# T2M_4_0.net
KiCad netlist of a schematic drawn in EAGLE
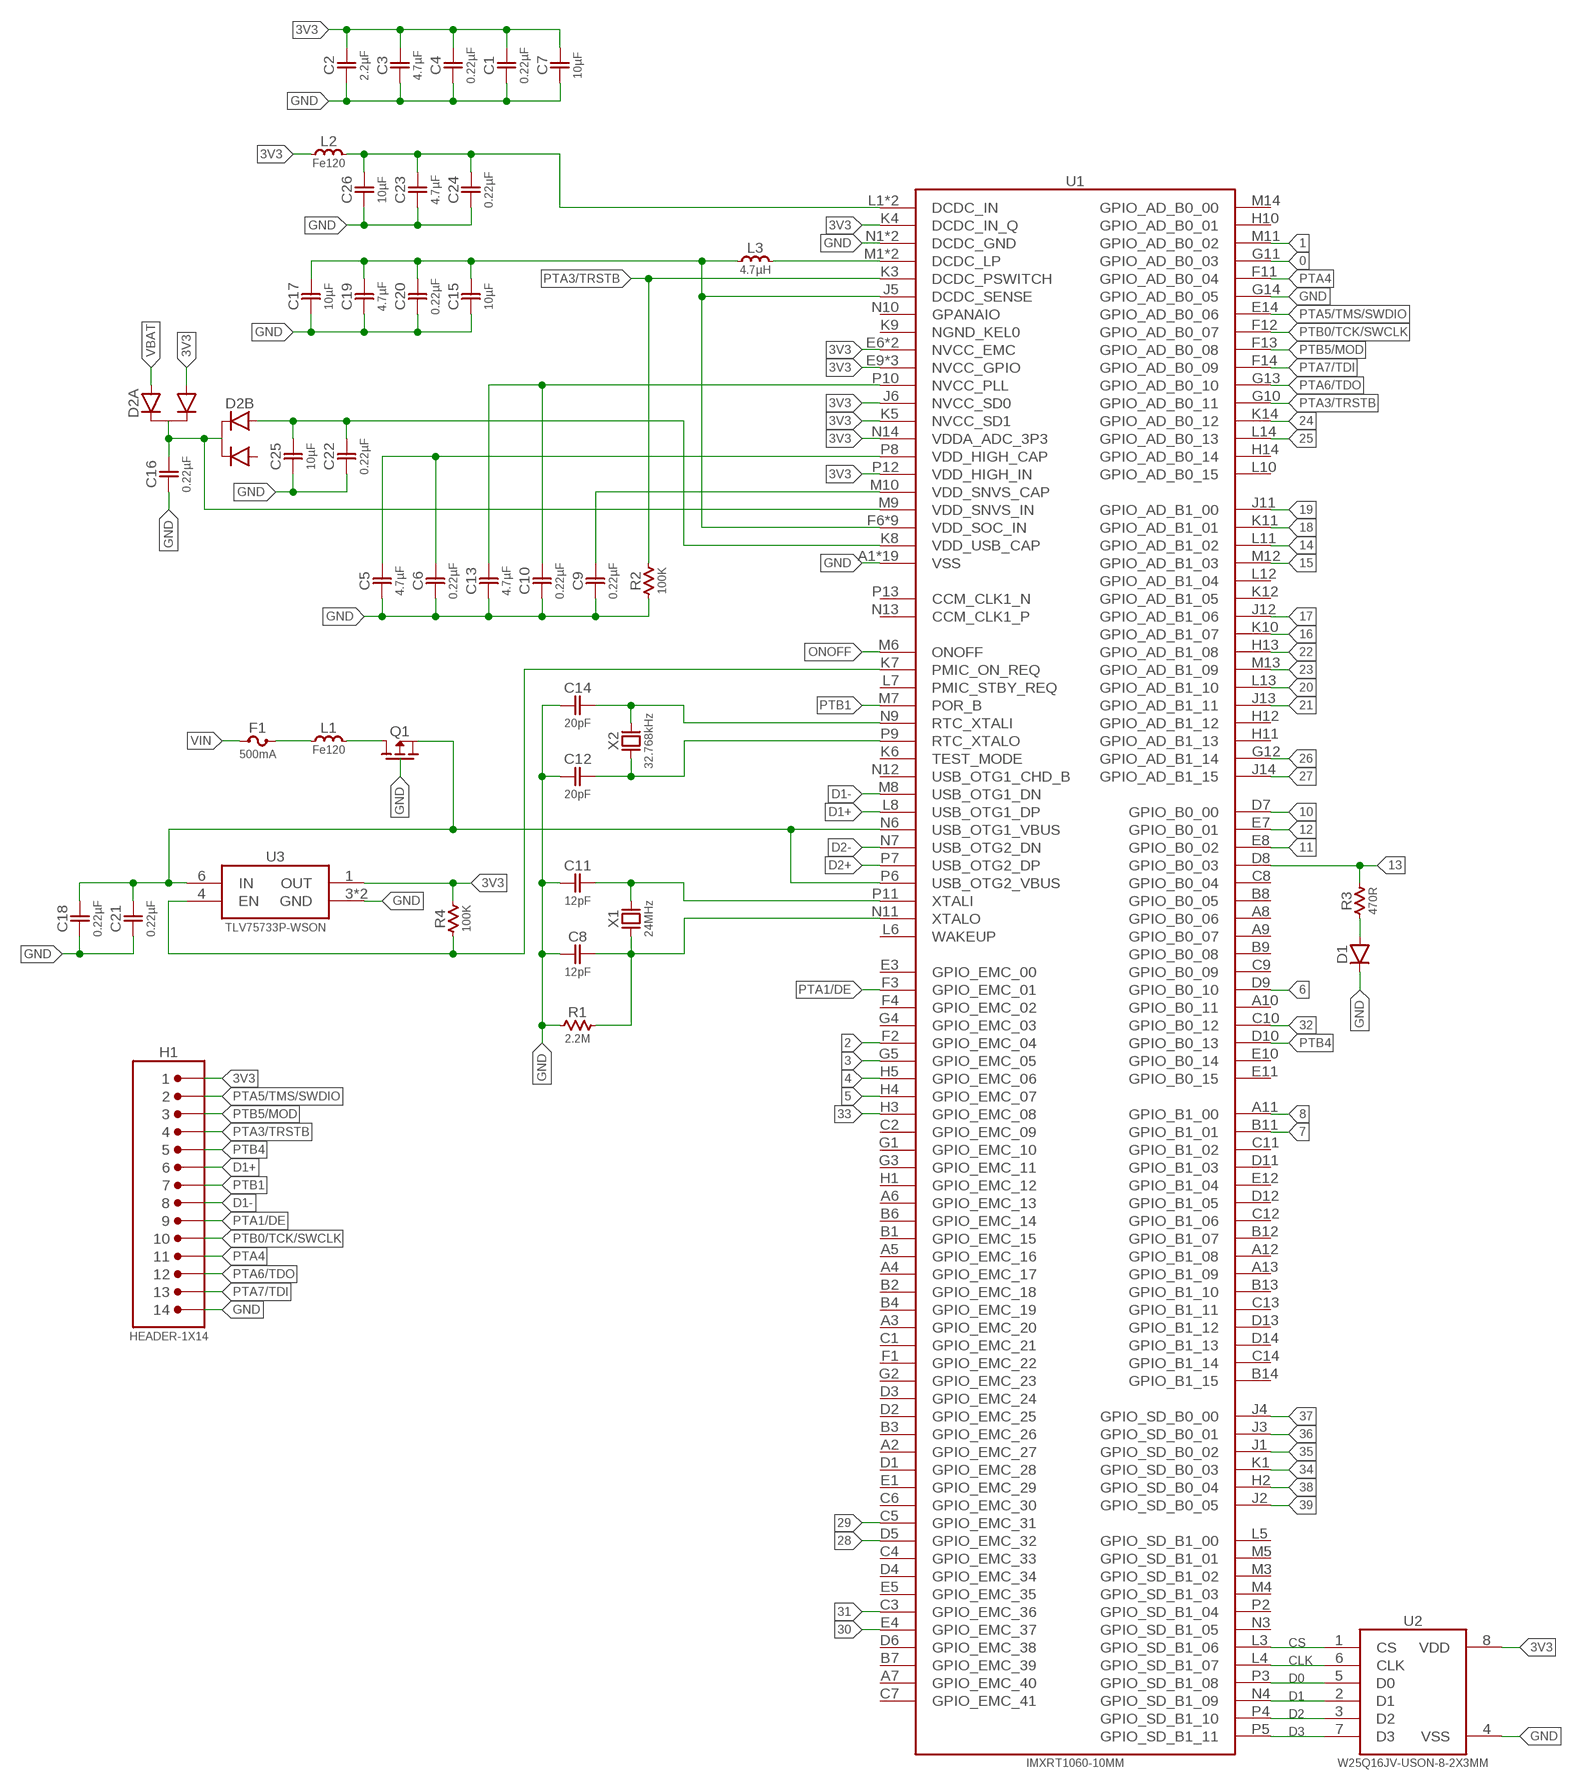
[diagram p0: schematic, sheet 1]
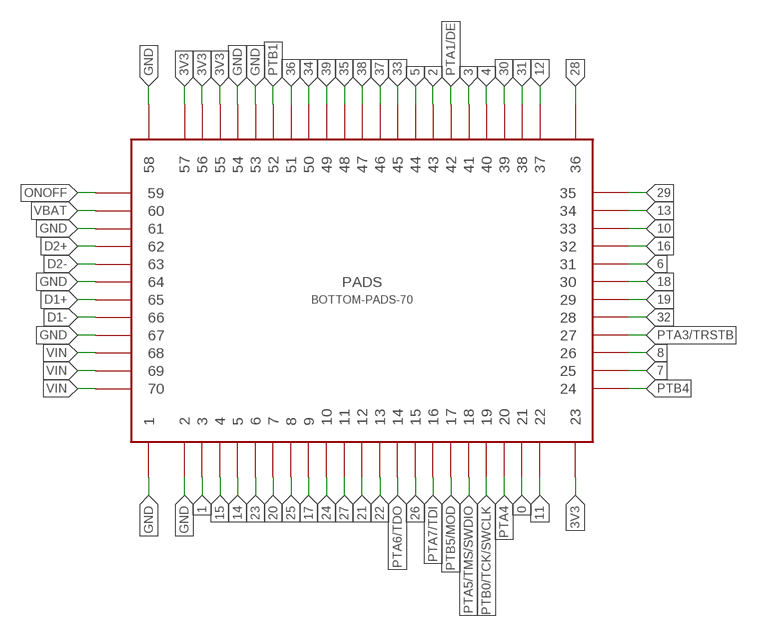
[diagram p1: schematic, sheet 2]

(export (version "E")
  (design (tool "Eeschema 10.0.6"))
  (components
    (comp (ref "C1")
      (value "0.22µF")
      (footprint "eagle-import:0402-NP")
      (libsource (lib "eagle-import") (part "CAP-NP-0402"))
    )
    (comp (ref "C2")
      (value "2.2µF")
      (footprint "eagle-import:0402-NP")
      (libsource (lib "eagle-import") (part "CAP-NP-0402"))
    )
    (comp (ref "C3")
      (value "4.7µF")
      (footprint "eagle-import:0402-NP")
      (libsource (lib "eagle-import") (part "CAP-NP-0402"))
    )
    (comp (ref "C4")
      (value "0.22µF")
      (footprint "eagle-import:0402-NP")
      (libsource (lib "eagle-import") (part "CAP-NP-0402"))
    )
    (comp (ref "C5")
      (value "4.7µF")
      (footprint "eagle-import:0402-NP")
      (libsource (lib "eagle-import") (part "CAP-NP-0402"))
    )
    (comp (ref "C6")
      (value "0.22µF")
      (footprint "eagle-import:0402-NP")
      (libsource (lib "eagle-import") (part "CAP-NP-0402"))
    )
    (comp (ref "C7")
      (value "10µF")
      (footprint "eagle-import:0603-NP")
      (libsource (lib "eagle-import") (part "CAP-NP-0603"))
    )
    (comp (ref "C8")
      (value "12pF")
      (footprint "eagle-import:0402-NP")
      (libsource (lib "eagle-import") (part "CAP-NP-0402"))
    )
    (comp (ref "C9")
      (value "0.22µF")
      (footprint "eagle-import:0402-NP")
      (libsource (lib "eagle-import") (part "CAP-NP-0402"))
    )
    (comp (ref "C10")
      (value "0.22µF")
      (footprint "eagle-import:0402-NP")
      (libsource (lib "eagle-import") (part "CAP-NP-0402"))
    )
    (comp (ref "C11")
      (value "12pF")
      (footprint "eagle-import:0402-NP")
      (libsource (lib "eagle-import") (part "CAP-NP-0402"))
    )
    (comp (ref "C12")
      (value "20pF")
      (footprint "eagle-import:0402-NP")
      (libsource (lib "eagle-import") (part "CAP-NP-0402"))
    )
    (comp (ref "C13")
      (value "4.7µF")
      (footprint "eagle-import:0402-NP")
      (libsource (lib "eagle-import") (part "CAP-NP-0402"))
    )
    (comp (ref "C14")
      (value "20pF")
      (footprint "eagle-import:0402-NP")
      (libsource (lib "eagle-import") (part "CAP-NP-0402"))
    )
    (comp (ref "C15")
      (value "10µF")
      (footprint "eagle-import:0603-NP")
      (libsource (lib "eagle-import") (part "CAP-NP-0603"))
    )
    (comp (ref "C16")
      (value "0.22µF")
      (footprint "eagle-import:0402-NP")
      (libsource (lib "eagle-import") (part "CAP-NP-0402"))
    )
    (comp (ref "C17")
      (value "10µF")
      (footprint "eagle-import:0603-NP")
      (libsource (lib "eagle-import") (part "CAP-NP-0603"))
    )
    (comp (ref "C18")
      (value "0.22µF")
      (footprint "eagle-import:0402-NP")
      (libsource (lib "eagle-import") (part "CAP-NP-0402"))
    )
    (comp (ref "C19")
      (value "4.7µF")
      (footprint "eagle-import:0402-NP")
      (libsource (lib "eagle-import") (part "CAP-NP-0402"))
    )
    (comp (ref "C20")
      (value "0.22µF")
      (footprint "eagle-import:0402-NP")
      (libsource (lib "eagle-import") (part "CAP-NP-0402"))
    )
    (comp (ref "C21")
      (value "0.22µF")
      (footprint "eagle-import:0402-NP")
      (libsource (lib "eagle-import") (part "CAP-NP-0402"))
    )
    (comp (ref "C22")
      (value "0.22µF")
      (footprint "eagle-import:0402-NP")
      (libsource (lib "eagle-import") (part "CAP-NP-0402"))
    )
    (comp (ref "C23")
      (value "4.7µF")
      (footprint "eagle-import:0402-NP")
      (libsource (lib "eagle-import") (part "CAP-NP-0402"))
    )
    (comp (ref "C24")
      (value "0.22µF")
      (footprint "eagle-import:0402-NP")
      (libsource (lib "eagle-import") (part "CAP-NP-0402"))
    )
    (comp (ref "C25")
      (value "10µF")
      (footprint "eagle-import:0603-NP")
      (libsource (lib "eagle-import") (part "CAP-NP-0603"))
    )
    (comp (ref "C26")
      (value "10µF")
      (footprint "eagle-import:0603-NP")
      (libsource (lib "eagle-import") (part "CAP-NP-0603"))
    )
    (comp (ref "D1")
      (value "DIODE-0402")
      (footprint "eagle-import:0402-P")
      (libsource (lib "eagle-import") (part "DIODE-0402"))
    )
    (comp (ref "D2")
      (value "BAT54C-2-SOT-666")
      (footprint "eagle-import:SOT-666")
      (libsource (lib "eagle-import") (part "BAT54C-2-SOT-666"))
    )
    (comp (ref "F1")
      (value "500mA")
      (footprint "eagle-import:0603-NP")
      (libsource (lib "eagle-import") (part "FUSE-0603"))
    )
    (comp (ref "H1")
      (value "HEADER-1X14")
      (footprint "eagle-import:2X7-1.27MM")
      (libsource (lib "eagle-import") (part "HEADER-1X14"))
    )
    (comp (ref "L1")
      (value "Fe120")
      (footprint "eagle-import:0402-NP")
      (libsource (lib "eagle-import") (part "INDUCTOR-0402"))
    )
    (comp (ref "L2")
      (value "Fe120")
      (footprint "eagle-import:0402-NP")
      (libsource (lib "eagle-import") (part "INDUCTOR-0402"))
    )
    (comp (ref "L3")
      (value "4.7µH")
      (footprint "eagle-import:0603-NP")
      (libsource (lib "eagle-import") (part "INDUCTOR-0603"))
    )
    (comp (ref "Q1")
      (value "MOSFET-P")
      (footprint "eagle-import:SOT-23")
      (libsource (lib "eagle-import") (part "MOSFET-P"))
    )
    (comp (ref "R1")
      (value "2.2M")
      (footprint "eagle-import:0402-NP")
      (libsource (lib "eagle-import") (part "RESISTOR-0402"))
    )
    (comp (ref "R2")
      (value "100K")
      (footprint "eagle-import:0402-NP")
      (libsource (lib "eagle-import") (part "RESISTOR-0402"))
    )
    (comp (ref "R3")
      (value "470R")
      (footprint "eagle-import:0402-NP")
      (libsource (lib "eagle-import") (part "RESISTOR-0402"))
    )
    (comp (ref "R4")
      (value "100K")
      (footprint "eagle-import:0402-NP")
      (libsource (lib "eagle-import") (part "RESISTOR-0402"))
    )
    (comp (ref "U1")
      (value "IMXRT1060-10MM")
      (footprint "eagle-import:BGA-196-10MM")
      (libsource (lib "eagle-import") (part "IMXRT1060-10MM"))
    )
    (comp (ref "U2")
      (value "W25Q16JV-USON-8-2X3MM")
      (footprint "eagle-import:USON-8-2X3MM")
      (libsource (lib "eagle-import") (part "W25Q16JV-USON-8-2X3MM"))
    )
    (comp (ref "U3")
      (value "TLV75733P-WSON")
      (footprint "eagle-import:WSON-6")
      (libsource (lib "eagle-import") (part "TLV75733P-WSON"))
    )
    (comp (ref "X1")
      (value "24MHz")
      (footprint "eagle-import:CRYSTAL-2X1.6MM")
      (libsource (lib "eagle-import") (part "CRYSTAL-2X1.6MM"))
    )
    (comp (ref "X2")
      (value "32.768kHz")
      (footprint "eagle-import:CRYSTAL-2X1.2MM")
      (libsource (lib "eagle-import") (part "CRYSTAL-2X1.2MM"))
    )
    (comp (ref "PADS")
      (value "BOTTOM-PADS-70")
      (footprint "eagle-import:BOTTOM-PADS-70")
      (libsource (lib "eagle-import") (part "BOTTOM-PADS-70"))
    )
  )
  (nets
    (net (code "1") (name "0") (class "Default")
      (node (ref "PADS") (pin "21") (pinfunction "21_21") (pintype "bidirectional"))
      (node (ref "U1") (pin "G11") (pinfunction "GPIO_AD_B0_03_G11") (pintype "bidirectional"))
    )
    (net (code "2") (name "1") (class "Default")
      (node (ref "PADS") (pin "3") (pinfunction "3_3") (pintype "bidirectional"))
      (node (ref "U1") (pin "M11") (pinfunction "GPIO_AD_B0_02_M11") (pintype "bidirectional"))
    )
    (net (code "3") (name "2") (class "Default")
      (node (ref "PADS") (pin "43") (pinfunction "43_43") (pintype "bidirectional"))
      (node (ref "U1") (pin "F2") (pinfunction "GPIO_EMC_04_F2") (pintype "bidirectional"))
    )
    (net (code "4") (name "3") (class "Default")
      (node (ref "PADS") (pin "41") (pinfunction "41_41") (pintype "bidirectional"))
      (node (ref "U1") (pin "G5") (pinfunction "GPIO_EMC_05_G5") (pintype "bidirectional"))
    )
    (net (code "5") (name "3V3") (class "Default")
      (node (ref "C1") (pin "2") (pinfunction "2_2") (pintype "bidirectional"))
      (node (ref "C2") (pin "2") (pinfunction "2_2") (pintype "bidirectional"))
      (node (ref "C3") (pin "2") (pinfunction "2_2") (pintype "bidirectional"))
      (node (ref "C4") (pin "2") (pinfunction "2_2") (pintype "bidirectional"))
      (node (ref "C7") (pin "2") (pinfunction "2_2") (pintype "bidirectional"))
      (node (ref "D2") (pin "2") (pinfunction "A2_2") (pintype "passive"))
      (node (ref "H1") (pin "1") (pinfunction "1_1") (pintype "bidirectional"))
      (node (ref "L2") (pin "1") (pinfunction "1_1") (pintype "passive"))
      (node (ref "PADS") (pin "23") (pinfunction "23_23") (pintype "bidirectional"))
      (node (ref "PADS") (pin "55") (pinfunction "55_55") (pintype "bidirectional"))
      (node (ref "PADS") (pin "56") (pinfunction "56_56") (pintype "bidirectional"))
      (node (ref "PADS") (pin "57") (pinfunction "57_57") (pintype "bidirectional"))
      (node (ref "R4") (pin "2") (pinfunction "2_2") (pintype "passive"))
      (node (ref "U1") (pin "E6") (pinfunction "NVCC_EMC_E6") (pintype "bidirectional"))
      (node (ref "U1") (pin "E9") (pinfunction "NVCC_GPIO_E9") (pintype "bidirectional"))
      (node (ref "U1") (pin "F10") (pinfunction "NVCC_GPIO_F10") (pintype "bidirectional"))
      (node (ref "U1") (pin "F5") (pinfunction "NVCC_EMC_F5") (pintype "bidirectional"))
      (node (ref "U1") (pin "J10") (pinfunction "NVCC_GPIO_J10") (pintype "bidirectional"))
      (node (ref "U1") (pin "J6") (pinfunction "NVCC_SD0_J6") (pintype "bidirectional"))
      (node (ref "U1") (pin "K4") (pinfunction "DCDC_IN_Q_K4") (pintype "bidirectional"))
      (node (ref "U1") (pin "K5") (pinfunction "NVCC_SD1_K5") (pintype "bidirectional"))
      (node (ref "U1") (pin "N14") (pinfunction "VDDA_ADC_3P3_N14") (pintype "bidirectional"))
      (node (ref "U1") (pin "P12") (pinfunction "VDD_HIGH_IN_P12") (pintype "bidirectional"))
      (node (ref "U2") (pin "8") (pinfunction "VDD_8") (pintype "bidirectional"))
      (node (ref "U3") (pin "1") (pinfunction "OUT_1") (pintype "bidirectional"))
    )
    (net (code "6") (name "4") (class "Default")
      (node (ref "PADS") (pin "40") (pinfunction "40_40") (pintype "bidirectional"))
      (node (ref "U1") (pin "H5") (pinfunction "GPIO_EMC_06_H5") (pintype "bidirectional"))
    )
    (net (code "7") (name "5") (class "Default")
      (node (ref "PADS") (pin "44") (pinfunction "44_44") (pintype "bidirectional"))
      (node (ref "U1") (pin "H4") (pinfunction "GPIO_EMC_07_H4") (pintype "bidirectional"))
    )
    (net (code "8") (name "6") (class "Default")
      (node (ref "PADS") (pin "31") (pinfunction "31_31") (pintype "bidirectional"))
      (node (ref "U1") (pin "D9") (pinfunction "GPIO_B0_10_D9") (pintype "bidirectional"))
    )
    (net (code "9") (name "7") (class "Default")
      (node (ref "PADS") (pin "25") (pinfunction "25_25") (pintype "bidirectional"))
      (node (ref "U1") (pin "B11") (pinfunction "GPIO_B1_01_B11") (pintype "bidirectional"))
    )
    (net (code "10") (name "8") (class "Default")
      (node (ref "PADS") (pin "26") (pinfunction "26_26") (pintype "bidirectional"))
      (node (ref "U1") (pin "A11") (pinfunction "GPIO_B1_00_A11") (pintype "bidirectional"))
    )
    (net (code "11") (name "10") (class "Default")
      (node (ref "PADS") (pin "33") (pinfunction "33_33") (pintype "bidirectional"))
      (node (ref "U1") (pin "D7") (pinfunction "GPIO_B0_00_D7") (pintype "bidirectional"))
    )
    (net (code "12") (name "11") (class "Default")
      (node (ref "PADS") (pin "22") (pinfunction "22_22") (pintype "bidirectional"))
      (node (ref "U1") (pin "E8") (pinfunction "GPIO_B0_02_E8") (pintype "bidirectional"))
    )
    (net (code "13") (name "12") (class "Default")
      (node (ref "PADS") (pin "37") (pinfunction "37_37") (pintype "bidirectional"))
      (node (ref "U1") (pin "E7") (pinfunction "GPIO_B0_01_E7") (pintype "bidirectional"))
    )
    (net (code "14") (name "13") (class "Default")
      (node (ref "PADS") (pin "34") (pinfunction "34_34") (pintype "bidirectional"))
      (node (ref "R3") (pin "2") (pinfunction "2_2") (pintype "passive"))
      (node (ref "U1") (pin "D8") (pinfunction "GPIO_B0_03_D8") (pintype "bidirectional"))
    )
    (net (code "15") (name "14") (class "Default")
      (node (ref "PADS") (pin "5") (pinfunction "5_5") (pintype "bidirectional"))
      (node (ref "U1") (pin "L11") (pinfunction "GPIO_AD_B1_02_L11") (pintype "bidirectional"))
    )
    (net (code "16") (name "15") (class "Default")
      (node (ref "PADS") (pin "4") (pinfunction "4_4") (pintype "bidirectional"))
      (node (ref "U1") (pin "M12") (pinfunction "GPIO_AD_B1_03_M12") (pintype "bidirectional"))
    )
    (net (code "17") (name "16") (class "Default")
      (node (ref "PADS") (pin "32") (pinfunction "32_32") (pintype "bidirectional"))
      (node (ref "U1") (pin "K10") (pinfunction "GPIO_AD_B1_07_K10") (pintype "bidirectional"))
    )
    (net (code "18") (name "17") (class "Default")
      (node (ref "PADS") (pin "9") (pinfunction "9_9") (pintype "bidirectional"))
      (node (ref "U1") (pin "J12") (pinfunction "GPIO_AD_B1_06_J12") (pintype "bidirectional"))
    )
    (net (code "19") (name "18") (class "Default")
      (node (ref "PADS") (pin "30") (pinfunction "30_30") (pintype "bidirectional"))
      (node (ref "U1") (pin "K11") (pinfunction "GPIO_AD_B1_01_K11") (pintype "bidirectional"))
    )
    (net (code "20") (name "19") (class "Default")
      (node (ref "PADS") (pin "29") (pinfunction "29_29") (pintype "bidirectional"))
      (node (ref "U1") (pin "J11") (pinfunction "GPIO_AD_B1_00_J11") (pintype "bidirectional"))
    )
    (net (code "21") (name "20") (class "Default")
      (node (ref "PADS") (pin "7") (pinfunction "7_7") (pintype "bidirectional"))
      (node (ref "U1") (pin "L13") (pinfunction "GPIO_AD_B1_10_L13") (pintype "bidirectional"))
    )
    (net (code "22") (name "21") (class "Default")
      (node (ref "PADS") (pin "12") (pinfunction "12_12") (pintype "bidirectional"))
      (node (ref "U1") (pin "J13") (pinfunction "GPIO_AD_B1_11_J13") (pintype "bidirectional"))
    )
    (net (code "23") (name "22") (class "Default")
      (node (ref "PADS") (pin "13") (pinfunction "13_13") (pintype "bidirectional"))
      (node (ref "U1") (pin "H13") (pinfunction "GPIO_AD_B1_08_H13") (pintype "bidirectional"))
    )
    (net (code "24") (name "23") (class "Default")
      (node (ref "PADS") (pin "6") (pinfunction "6_6") (pintype "bidirectional"))
      (node (ref "U1") (pin "M13") (pinfunction "GPIO_AD_B1_09_M13") (pintype "bidirectional"))
    )
    (net (code "25") (name "24") (class "Default")
      (node (ref "PADS") (pin "10") (pinfunction "10_10") (pintype "bidirectional"))
      (node (ref "U1") (pin "K14") (pinfunction "GPIO_AD_B0_12_K14") (pintype "bidirectional"))
    )
    (net (code "26") (name "25") (class "Default")
      (node (ref "PADS") (pin "8") (pinfunction "8_8") (pintype "bidirectional"))
      (node (ref "U1") (pin "L14") (pinfunction "GPIO_AD_B0_13_L14") (pintype "bidirectional"))
    )
    (net (code "27") (name "26") (class "Default")
      (node (ref "PADS") (pin "15") (pinfunction "15_15") (pintype "bidirectional"))
      (node (ref "U1") (pin "G12") (pinfunction "GPIO_AD_B1_14_G12") (pintype "bidirectional"))
    )
    (net (code "28") (name "27") (class "Default")
      (node (ref "PADS") (pin "11") (pinfunction "11_11") (pintype "bidirectional"))
      (node (ref "U1") (pin "J14") (pinfunction "GPIO_AD_B1_15_J14") (pintype "bidirectional"))
    )
    (net (code "29") (name "28") (class "Default")
      (node (ref "PADS") (pin "36") (pinfunction "36_36") (pintype "bidirectional"))
      (node (ref "U1") (pin "D5") (pinfunction "GPIO_EMC_32_D5") (pintype "bidirectional"))
    )
    (net (code "30") (name "29") (class "Default")
      (node (ref "PADS") (pin "35") (pinfunction "35_35") (pintype "bidirectional"))
      (node (ref "U1") (pin "C5") (pinfunction "GPIO_EMC_31_C5") (pintype "bidirectional"))
    )
    (net (code "31") (name "30") (class "Default")
      (node (ref "PADS") (pin "39") (pinfunction "39_39") (pintype "bidirectional"))
      (node (ref "U1") (pin "E4") (pinfunction "GPIO_EMC_37_E4") (pintype "bidirectional"))
    )
    (net (code "32") (name "31") (class "Default")
      (node (ref "PADS") (pin "38") (pinfunction "38_38") (pintype "bidirectional"))
      (node (ref "U1") (pin "C3") (pinfunction "GPIO_EMC_36_C3") (pintype "bidirectional"))
    )
    (net (code "33") (name "32") (class "Default")
      (node (ref "PADS") (pin "28") (pinfunction "28_28") (pintype "bidirectional"))
      (node (ref "U1") (pin "C10") (pinfunction "GPIO_B0_12_C10") (pintype "bidirectional"))
    )
    (net (code "34") (name "33") (class "Default")
      (node (ref "PADS") (pin "45") (pinfunction "45_45") (pintype "bidirectional"))
      (node (ref "U1") (pin "H3") (pinfunction "GPIO_EMC_08_H3") (pintype "bidirectional"))
    )
    (net (code "35") (name "34") (class "Default")
      (node (ref "PADS") (pin "50") (pinfunction "50_50") (pintype "bidirectional"))
      (node (ref "U1") (pin "K1") (pinfunction "GPIO_SD_B0_03_K1") (pintype "bidirectional"))
    )
    (net (code "36") (name "35") (class "Default")
      (node (ref "PADS") (pin "48") (pinfunction "48_48") (pintype "bidirectional"))
      (node (ref "U1") (pin "J1") (pinfunction "GPIO_SD_B0_02_J1") (pintype "bidirectional"))
    )
    (net (code "37") (name "36") (class "Default")
      (node (ref "PADS") (pin "51") (pinfunction "51_51") (pintype "bidirectional"))
      (node (ref "U1") (pin "J3") (pinfunction "GPIO_SD_B0_01_J3") (pintype "bidirectional"))
    )
    (net (code "38") (name "37") (class "Default")
      (node (ref "PADS") (pin "46") (pinfunction "46_46") (pintype "bidirectional"))
      (node (ref "U1") (pin "J4") (pinfunction "GPIO_SD_B0_00_J4") (pintype "bidirectional"))
    )
    (net (code "39") (name "38") (class "Default")
      (node (ref "PADS") (pin "47") (pinfunction "47_47") (pintype "bidirectional"))
      (node (ref "U1") (pin "H2") (pinfunction "GPIO_SD_B0_04_H2") (pintype "bidirectional"))
    )
    (net (code "40") (name "39") (class "Default")
      (node (ref "PADS") (pin "49") (pinfunction "49_49") (pintype "bidirectional"))
      (node (ref "U1") (pin "J2") (pinfunction "GPIO_SD_B0_05_J2") (pintype "bidirectional"))
    )
    (net (code "41") (name "CLK") (class "Default")
      (node (ref "U1") (pin "L4") (pinfunction "GPIO_SD_B1_07_L4") (pintype "bidirectional"))
      (node (ref "U2") (pin "6") (pinfunction "CLK_6") (pintype "bidirectional"))
    )
    (net (code "42") (name "CS") (class "Default")
      (node (ref "U1") (pin "L3") (pinfunction "GPIO_SD_B1_06_L3") (pintype "bidirectional"))
      (node (ref "U2") (pin "1") (pinfunction "CS_1") (pintype "bidirectional"))
    )
    (net (code "43") (name "D0") (class "Default")
      (node (ref "U1") (pin "P3") (pinfunction "GPIO_SD_B1_08_P3") (pintype "bidirectional"))
      (node (ref "U2") (pin "5") (pinfunction "D0_5") (pintype "bidirectional"))
    )
    (net (code "44") (name "D1") (class "Default")
      (node (ref "U1") (pin "N4") (pinfunction "GPIO_SD_B1_09_N4") (pintype "bidirectional"))
      (node (ref "U2") (pin "2") (pinfunction "D1_2") (pintype "bidirectional"))
    )
    (net (code "45") (name "D1+") (class "Default")
      (node (ref "H1") (pin "6") (pinfunction "6_6") (pintype "bidirectional"))
      (node (ref "PADS") (pin "65") (pinfunction "65_65") (pintype "bidirectional"))
      (node (ref "U1") (pin "L8") (pinfunction "USB_OTG1_DP_L8") (pintype "bidirectional"))
    )
    (net (code "46") (name "D1-") (class "Default")
      (node (ref "H1") (pin "8") (pinfunction "8_8") (pintype "bidirectional"))
      (node (ref "PADS") (pin "66") (pinfunction "66_66") (pintype "bidirectional"))
      (node (ref "U1") (pin "M8") (pinfunction "USB_OTG1_DN_M8") (pintype "bidirectional"))
    )
    (net (code "47") (name "D2") (class "Default")
      (node (ref "U1") (pin "P4") (pinfunction "GPIO_SD_B1_10_P4") (pintype "bidirectional"))
      (node (ref "U2") (pin "3") (pinfunction "D2_3") (pintype "bidirectional"))
    )
    (net (code "48") (name "D2+") (class "Default")
      (node (ref "PADS") (pin "62") (pinfunction "62_62") (pintype "bidirectional"))
      (node (ref "U1") (pin "P7") (pinfunction "USB_OTG2_DP_P7") (pintype "bidirectional"))
    )
    (net (code "49") (name "D2-") (class "Default")
      (node (ref "PADS") (pin "63") (pinfunction "63_63") (pintype "bidirectional"))
      (node (ref "U1") (pin "N7") (pinfunction "USB_OTG2_DN_N7") (pintype "bidirectional"))
    )
    (net (code "50") (name "D3") (class "Default")
      (node (ref "U1") (pin "P5") (pinfunction "GPIO_SD_B1_11_P5") (pintype "bidirectional"))
      (node (ref "U2") (pin "7") (pinfunction "D3_7") (pintype "bidirectional"))
    )
    (net (code "51") (name "GND") (class "Default")
      (node (ref "C1") (pin "1") (pinfunction "1_1") (pintype "bidirectional"))
      (node (ref "C10") (pin "1") (pinfunction "1_1") (pintype "bidirectional"))
      (node (ref "C11") (pin "1") (pinfunction "1_1") (pintype "bidirectional"))
      (node (ref "C12") (pin "1") (pinfunction "1_1") (pintype "bidirectional"))
      (node (ref "C13") (pin "1") (pinfunction "1_1") (pintype "bidirectional"))
      (node (ref "C14") (pin "1") (pinfunction "1_1") (pintype "bidirectional"))
      (node (ref "C15") (pin "1") (pinfunction "1_1") (pintype "bidirectional"))
      (node (ref "C16") (pin "1") (pinfunction "1_1") (pintype "bidirectional"))
      (node (ref "C17") (pin "1") (pinfunction "1_1") (pintype "bidirectional"))
      (node (ref "C18") (pin "1") (pinfunction "1_1") (pintype "bidirectional"))
      (node (ref "C19") (pin "1") (pinfunction "1_1") (pintype "bidirectional"))
      (node (ref "C2") (pin "1") (pinfunction "1_1") (pintype "bidirectional"))
      (node (ref "C20") (pin "1") (pinfunction "1_1") (pintype "bidirectional"))
      (node (ref "C21") (pin "1") (pinfunction "1_1") (pintype "bidirectional"))
      (node (ref "C22") (pin "1") (pinfunction "1_1") (pintype "bidirectional"))
      (node (ref "C23") (pin "1") (pinfunction "1_1") (pintype "bidirectional"))
      (node (ref "C24") (pin "1") (pinfunction "1_1") (pintype "bidirectional"))
      (node (ref "C25") (pin "1") (pinfunction "1_1") (pintype "bidirectional"))
      (node (ref "C26") (pin "1") (pinfunction "1_1") (pintype "bidirectional"))
      (node (ref "C3") (pin "1") (pinfunction "1_1") (pintype "bidirectional"))
      (node (ref "C4") (pin "1") (pinfunction "1_1") (pintype "bidirectional"))
      (node (ref "C5") (pin "1") (pinfunction "1_1") (pintype "bidirectional"))
      (node (ref "C6") (pin "1") (pinfunction "1_1") (pintype "bidirectional"))
      (node (ref "C7") (pin "1") (pinfunction "1_1") (pintype "bidirectional"))
      (node (ref "C8") (pin "1") (pinfunction "1_1") (pintype "bidirectional"))
      (node (ref "C9") (pin "1") (pinfunction "1_1") (pintype "bidirectional"))
      (node (ref "D1") (pin "C") (pinfunction "C_C") (pintype "passive"))
      (node (ref "H1") (pin "14") (pinfunction "14_14") (pintype "bidirectional"))
      (node (ref "PADS") (pin "1") (pinfunction "1_1") (pintype "bidirectional"))
      (node (ref "PADS") (pin "2") (pinfunction "2_2") (pintype "bidirectional"))
      (node (ref "PADS") (pin "53") (pinfunction "53_53") (pintype "bidirectional"))
      (node (ref "PADS") (pin "54") (pinfunction "54_54") (pintype "bidirectional"))
      (node (ref "PADS") (pin "58") (pinfunction "58_58") (pintype "bidirectional"))
      (node (ref "PADS") (pin "61") (pinfunction "61_61") (pintype "bidirectional"))
      (node (ref "PADS") (pin "64") (pinfunction "64_64") (pintype "bidirectional"))
      (node (ref "PADS") (pin "67") (pinfunction "67_67") (pintype "bidirectional"))
      (node (ref "Q1") (pin "1") (pinfunction "G_1") (pintype "bidirectional"))
      (node (ref "R1") (pin "1") (pinfunction "1_1") (pintype "passive"))
      (node (ref "R2") (pin "1") (pinfunction "1_1") (pintype "passive"))
      (node (ref "U1") (pin "A1") (pinfunction "VSS_A1") (pintype "bidirectional"))
      (node (ref "U1") (pin "A14") (pinfunction "VSS_A14") (pintype "bidirectional"))
      (node (ref "U1") (pin "B10") (pinfunction "VSS_B10") (pintype "bidirectional"))
      (node (ref "U1") (pin "B5") (pinfunction "VSS_B5") (pintype "bidirectional"))
      (node (ref "U1") (pin "E13") (pinfunction "VSS_E13") (pintype "bidirectional"))
      (node (ref "U1") (pin "E2") (pinfunction "VSS_E2") (pintype "bidirectional"))
      (node (ref "U1") (pin "G14") (pinfunction "GPIO_AD_B0_05_G14") (pintype "bidirectional"))
      (node (ref "U1") (pin "G7") (pinfunction "VSS_G7") (pintype "bidirectional"))
      (node (ref "U1") (pin "G8") (pinfunction "VSS_G8") (pintype "bidirectional"))
      (node (ref "U1") (pin "H7") (pinfunction "VSS_H7") (pintype "bidirectional"))
      (node (ref "U1") (pin "H8") (pinfunction "VSS_H8") (pintype "bidirectional"))
      (node (ref "U1") (pin "J7") (pinfunction "VSS_J7") (pintype "bidirectional"))
      (node (ref "U1") (pin "J8") (pinfunction "VSS_J8") (pintype "bidirectional"))
      (node (ref "U1") (pin "K13") (pinfunction "VSS_K13") (pintype "bidirectional"))
      (node (ref "U1") (pin "K2") (pinfunction "VSS_K2") (pintype "bidirectional"))
      (node (ref "U1") (pin "L9") (pinfunction "VSS_L9") (pintype "bidirectional"))
      (node (ref "U1") (pin "N1") (pinfunction "DCDC_GND_N1") (pintype "bidirectional"))
      (node (ref "U1") (pin "N2") (pinfunction "DCDC_GND_N2") (pintype "bidirectional"))
      (node (ref "U1") (pin "N5") (pinfunction "VSS_N5") (pintype "bidirectional"))
      (node (ref "U1") (pin "N8") (pinfunction "VSS_N8") (pintype "bidirectional"))
      (node (ref "U1") (pin "P1") (pinfunction "VSS_P1") (pintype "bidirectional"))
      (node (ref "U1") (pin "P14") (pinfunction "VSS_P14") (pintype "bidirectional"))
      (node (ref "U2") (pin "4") (pinfunction "VSS_4") (pintype "bidirectional"))
      (node (ref "U3") (pin "3") (pinfunction "GND_3") (pintype "bidirectional"))
      (node (ref "U3") (pin "7") (pinfunction "GND_7") (pintype "bidirectional"))
    )
    (net (code "52") (name "Net-(C23-Pad2)") (class "Default")
      (node (ref "C23") (pin "2") (pinfunction "2_2") (pintype "bidirectional"))
      (node (ref "C24") (pin "2") (pinfunction "2_2") (pintype "bidirectional"))
      (node (ref "C26") (pin "2") (pinfunction "2_2") (pintype "bidirectional"))
      (node (ref "L2") (pin "2") (pinfunction "2_2") (pintype "passive"))
      (node (ref "U1") (pin "L1") (pinfunction "DCDC_IN_L1") (pintype "bidirectional"))
      (node (ref "U1") (pin "L2") (pinfunction "DCDC_IN_L2") (pintype "bidirectional"))
    )
    (net (code "53") (name "Net-(D1-PadA)") (class "Default")
      (node (ref "D1") (pin "A") (pinfunction "A_A") (pintype "passive"))
      (node (ref "R3") (pin "1") (pinfunction "1_1") (pintype "passive"))
    )
    (net (code "54") (name "Net-(D2A-CC)") (class "Default")
      (node (ref "C16") (pin "2") (pinfunction "2_2") (pintype "bidirectional"))
      (node (ref "D2") (pin "3") (pinfunction "CC_3") (pintype "passive"))
      (node (ref "D2") (pin "6") (pinfunction "CC_6") (pintype "passive"))
      (node (ref "U1") (pin "M9") (pinfunction "VDD_SNVS_IN_M9") (pintype "bidirectional"))
    )
    (net (code "55") (name "Net-(D2B-A1)") (class "Default")
      (node (ref "C22") (pin "2") (pinfunction "2_2") (pintype "bidirectional"))
      (node (ref "C25") (pin "2") (pinfunction "2_2") (pintype "bidirectional"))
      (node (ref "D2") (pin "4") (pinfunction "A1_4") (pintype "passive"))
      (node (ref "U1") (pin "K8") (pinfunction "VDD_USB_CAP_K8") (pintype "bidirectional"))
    )
    (net (code "56") (name "Net-(F1-Pad2)") (class "Default")
      (node (ref "F1") (pin "2") (pinfunction "2_2") (pintype "passive"))
      (node (ref "L1") (pin "1") (pinfunction "1_1") (pintype "passive"))
    )
    (net (code "57") (name "Net-(L3-Pad2)") (class "Default")
      (node (ref "L3") (pin "2") (pinfunction "2_2") (pintype "passive"))
      (node (ref "U1") (pin "M1") (pinfunction "DCDC_LP_M1") (pintype "bidirectional"))
      (node (ref "U1") (pin "M2") (pinfunction "DCDC_LP_M2") (pintype "bidirectional"))
    )
    (net (code "58") (name "Net-(Q1-D)") (class "Default")
      (node (ref "L1") (pin "2") (pinfunction "2_2") (pintype "passive"))
      (node (ref "Q1") (pin "3") (pinfunction "D_3") (pintype "bidirectional"))
    )
    (net (code "59") (name "Net-(Q1-S)") (class "Default")
      (node (ref "C18") (pin "2") (pinfunction "2_2") (pintype "bidirectional"))
      (node (ref "C21") (pin "2") (pinfunction "2_2") (pintype "bidirectional"))
      (node (ref "Q1") (pin "2") (pinfunction "S_2") (pintype "bidirectional"))
      (node (ref "U1") (pin "N6") (pinfunction "USB_OTG1_VBUS_N6") (pintype "bidirectional"))
      (node (ref "U1") (pin "P6") (pinfunction "USB_OTG2_VBUS_P6") (pintype "bidirectional"))
      (node (ref "U3") (pin "6") (pinfunction "IN_6") (pintype "bidirectional"))
    )
    (net (code "60") (name "Net-(U1-DCDC_SENSE)") (class "Default")
      (node (ref "C15") (pin "2") (pinfunction "2_2") (pintype "bidirectional"))
      (node (ref "C17") (pin "2") (pinfunction "2_2") (pintype "bidirectional"))
      (node (ref "C19") (pin "2") (pinfunction "2_2") (pintype "bidirectional"))
      (node (ref "C20") (pin "2") (pinfunction "2_2") (pintype "bidirectional"))
      (node (ref "L3") (pin "1") (pinfunction "1_1") (pintype "passive"))
      (node (ref "U1") (pin "F6") (pinfunction "VDD_SOC_IN_F6") (pintype "bidirectional"))
      (node (ref "U1") (pin "F7") (pinfunction "VDD_SOC_IN_F7") (pintype "bidirectional"))
      (node (ref "U1") (pin "F8") (pinfunction "VDD_SOC_IN_F8") (pintype "bidirectional"))
      (node (ref "U1") (pin "F9") (pinfunction "VDD_SOC_IN_F9") (pintype "bidirectional"))
      (node (ref "U1") (pin "G6") (pinfunction "VDD_SOC_IN_G6") (pintype "bidirectional"))
      (node (ref "U1") (pin "G9") (pinfunction "VDD_SOC_IN_G9") (pintype "bidirectional"))
      (node (ref "U1") (pin "H6") (pinfunction "VDD_SOC_IN_H6") (pintype "bidirectional"))
      (node (ref "U1") (pin "H9") (pinfunction "VDD_SOC_IN_H9") (pintype "bidirectional"))
      (node (ref "U1") (pin "J5") (pinfunction "DCDC_SENSE_J5") (pintype "bidirectional"))
      (node (ref "U1") (pin "J9") (pinfunction "VDD_SOC_IN_J9") (pintype "bidirectional"))
    )
    (net (code "61") (name "Net-(U1-NVCC_PLL)") (class "Default")
      (node (ref "C10") (pin "2") (pinfunction "2_2") (pintype "bidirectional"))
      (node (ref "C13") (pin "2") (pinfunction "2_2") (pintype "bidirectional"))
      (node (ref "U1") (pin "P10") (pinfunction "NVCC_PLL_P10") (pintype "bidirectional"))
    )
    (net (code "62") (name "Net-(U1-PMIC_ON_REQ)") (class "Default")
      (node (ref "R4") (pin "1") (pinfunction "1_1") (pintype "passive"))
      (node (ref "U1") (pin "K7") (pinfunction "PMIC_ON_REQ_K7") (pintype "bidirectional"))
      (node (ref "U3") (pin "4") (pinfunction "EN_4") (pintype "bidirectional"))
    )
    (net (code "63") (name "Net-(U1-RTC_XTALI)") (class "Default")
      (node (ref "C14") (pin "2") (pinfunction "2_2") (pintype "bidirectional"))
      (node (ref "U1") (pin "N9") (pinfunction "RTC_XTALI_N9") (pintype "bidirectional"))
      (node (ref "X2") (pin "2") (pinfunction "2_2") (pintype "bidirectional"))
    )
    (net (code "64") (name "Net-(U1-RTC_XTALO)") (class "Default")
      (node (ref "C12") (pin "2") (pinfunction "2_2") (pintype "bidirectional"))
      (node (ref "U1") (pin "P9") (pinfunction "RTC_XTALO_P9") (pintype "bidirectional"))
      (node (ref "X2") (pin "1") (pinfunction "1_1") (pintype "bidirectional"))
    )
    (net (code "65") (name "Net-(U1-VDD_HIGH_CAP)") (class "Default")
      (node (ref "C5") (pin "2") (pinfunction "2_2") (pintype "bidirectional"))
      (node (ref "C6") (pin "2") (pinfunction "2_2") (pintype "bidirectional"))
      (node (ref "U1") (pin "P8") (pinfunction "VDD_HIGH_CAP_P8") (pintype "bidirectional"))
    )
    (net (code "66") (name "Net-(U1-VDD_SNVS_CAP)") (class "Default")
      (node (ref "C9") (pin "2") (pinfunction "2_2") (pintype "bidirectional"))
      (node (ref "U1") (pin "M10") (pinfunction "VDD_SNVS_CAP_M10") (pintype "bidirectional"))
    )
    (net (code "67") (name "Net-(U1-XTALI)") (class "Default")
      (node (ref "C11") (pin "2") (pinfunction "2_2") (pintype "bidirectional"))
      (node (ref "U1") (pin "P11") (pinfunction "XTALI_P11") (pintype "bidirectional"))
      (node (ref "X1") (pin "3") (pinfunction "2_3") (pintype "bidirectional"))
    )
    (net (code "68") (name "Net-(U1-XTALO)") (class "Default")
      (node (ref "C8") (pin "2") (pinfunction "2_2") (pintype "bidirectional"))
      (node (ref "R1") (pin "2") (pinfunction "2_2") (pintype "passive"))
      (node (ref "U1") (pin "N11") (pinfunction "XTALO_N11") (pintype "bidirectional"))
      (node (ref "X1") (pin "1") (pinfunction "1_1") (pintype "bidirectional"))
    )
    (net (code "69") (name "ONOFF") (class "Default")
      (node (ref "PADS") (pin "59") (pinfunction "59_59") (pintype "bidirectional"))
      (node (ref "U1") (pin "M6") (pinfunction "ONOFF_M6") (pintype "bidirectional"))
    )
    (net (code "70") (name "PTA1{slash}DE") (class "Default")
      (node (ref "H1") (pin "9") (pinfunction "9_9") (pintype "bidirectional"))
      (node (ref "PADS") (pin "42") (pinfunction "42_42") (pintype "bidirectional"))
      (node (ref "U1") (pin "F3") (pinfunction "GPIO_EMC_01_F3") (pintype "bidirectional"))
    )
    (net (code "71") (name "PTA3{slash}TRSTB") (class "Default")
      (node (ref "H1") (pin "4") (pinfunction "4_4") (pintype "bidirectional"))
      (node (ref "PADS") (pin "27") (pinfunction "27_27") (pintype "bidirectional"))
      (node (ref "R2") (pin "2") (pinfunction "2_2") (pintype "passive"))
      (node (ref "U1") (pin "G10") (pinfunction "GPIO_AD_B0_11_G10") (pintype "bidirectional"))
      (node (ref "U1") (pin "K3") (pinfunction "DCDC_PSWITCH_K3") (pintype "bidirectional"))
    )
    (net (code "72") (name "PTA4") (class "Default")
      (node (ref "H1") (pin "11") (pinfunction "11_11") (pintype "bidirectional"))
      (node (ref "PADS") (pin "20") (pinfunction "20_20") (pintype "bidirectional"))
      (node (ref "U1") (pin "F11") (pinfunction "GPIO_AD_B0_04_F11") (pintype "bidirectional"))
    )
    (net (code "73") (name "PTA5{slash}TMS{slash}SWDIO") (class "Default")
      (node (ref "H1") (pin "2") (pinfunction "2_2") (pintype "bidirectional"))
      (node (ref "PADS") (pin "18") (pinfunction "18_18") (pintype "bidirectional"))
      (node (ref "U1") (pin "E14") (pinfunction "GPIO_AD_B0_06_E14") (pintype "bidirectional"))
    )
    (net (code "74") (name "PTA6{slash}TDO") (class "Default")
      (node (ref "H1") (pin "12") (pinfunction "12_12") (pintype "bidirectional"))
      (node (ref "PADS") (pin "14") (pinfunction "14_14") (pintype "bidirectional"))
      (node (ref "U1") (pin "G13") (pinfunction "GPIO_AD_B0_10_G13") (pintype "bidirectional"))
    )
    (net (code "75") (name "PTA7{slash}TDI") (class "Default")
      (node (ref "H1") (pin "13") (pinfunction "13_13") (pintype "bidirectional"))
      (node (ref "PADS") (pin "16") (pinfunction "16_16") (pintype "bidirectional"))
      (node (ref "U1") (pin "F14") (pinfunction "GPIO_AD_B0_09_F14") (pintype "bidirectional"))
    )
    (net (code "76") (name "PTB0{slash}TCK{slash}SWCLK") (class "Default")
      (node (ref "H1") (pin "10") (pinfunction "10_10") (pintype "bidirectional"))
      (node (ref "PADS") (pin "19") (pinfunction "19_19") (pintype "bidirectional"))
      (node (ref "U1") (pin "F12") (pinfunction "GPIO_AD_B0_07_F12") (pintype "bidirectional"))
    )
    (net (code "77") (name "PTB1") (class "Default")
      (node (ref "H1") (pin "7") (pinfunction "7_7") (pintype "bidirectional"))
      (node (ref "PADS") (pin "52") (pinfunction "52_52") (pintype "bidirectional"))
      (node (ref "U1") (pin "M7") (pinfunction "POR_B_M7") (pintype "bidirectional"))
    )
    (net (code "78") (name "PTB4") (class "Default")
      (node (ref "H1") (pin "5") (pinfunction "5_5") (pintype "bidirectional"))
      (node (ref "PADS") (pin "24") (pinfunction "24_24") (pintype "bidirectional"))
      (node (ref "U1") (pin "D10") (pinfunction "GPIO_B0_13_D10") (pintype "bidirectional"))
    )
    (net (code "79") (name "PTB5{slash}MOD") (class "Default")
      (node (ref "H1") (pin "3") (pinfunction "3_3") (pintype "bidirectional"))
      (node (ref "PADS") (pin "17") (pinfunction "17_17") (pintype "bidirectional"))
      (node (ref "U1") (pin "F13") (pinfunction "GPIO_AD_B0_08_F13") (pintype "bidirectional"))
    )
    (net (code "80") (name "VBAT") (class "Default")
      (node (ref "D2") (pin "1") (pinfunction "A1_1") (pintype "passive"))
      (node (ref "PADS") (pin "60") (pinfunction "60_60") (pintype "bidirectional"))
    )
    (net (code "81") (name "VIN") (class "Default")
      (node (ref "F1") (pin "1") (pinfunction "1_1") (pintype "passive"))
      (node (ref "PADS") (pin "68") (pinfunction "68_68") (pintype "bidirectional"))
      (node (ref "PADS") (pin "69") (pinfunction "69_69") (pintype "bidirectional"))
      (node (ref "PADS") (pin "70") (pinfunction "70_70") (pintype "bidirectional"))
    )
    (net (code "82") (name "unconnected-(D2B-A2-Pad5)") (class "Default")
      (node (ref "D2") (pin "5") (pinfunction "A2_5") (pintype "passive"))
    )
    (net (code "83") (name "unconnected-(U1-CCM_CLK1_N-PadP13)") (class "Default")
      (node (ref "U1") (pin "P13") (pinfunction "CCM_CLK1_N_P13") (pintype "bidirectional"))
    )
    (net (code "84") (name "unconnected-(U1-CCM_CLK1_P-PadN13)") (class "Default")
      (node (ref "U1") (pin "N13") (pinfunction "CCM_CLK1_P_N13") (pintype "bidirectional"))
    )
    (net (code "85") (name "unconnected-(U1-GPANAIO-PadN10)") (class "Default")
      (node (ref "U1") (pin "N10") (pinfunction "GPANAIO_N10") (pintype "bidirectional"))
    )
    (net (code "86") (name "unconnected-(U1-GPIO_AD_B0_00-PadM14)") (class "Default")
      (node (ref "U1") (pin "M14") (pinfunction "GPIO_AD_B0_00_M14") (pintype "bidirectional"))
    )
    (net (code "87") (name "unconnected-(U1-GPIO_AD_B0_01-PadH10)") (class "Default")
      (node (ref "U1") (pin "H10") (pinfunction "GPIO_AD_B0_01_H10") (pintype "bidirectional"))
    )
    (net (code "88") (name "unconnected-(U1-GPIO_AD_B0_14-PadH14)") (class "Default")
      (node (ref "U1") (pin "H14") (pinfunction "GPIO_AD_B0_14_H14") (pintype "bidirectional"))
    )
    (net (code "89") (name "unconnected-(U1-GPIO_AD_B0_15-PadL10)") (class "Default")
      (node (ref "U1") (pin "L10") (pinfunction "GPIO_AD_B0_15_L10") (pintype "bidirectional"))
    )
    (net (code "90") (name "unconnected-(U1-GPIO_AD_B1_04-PadL12)") (class "Default")
      (node (ref "U1") (pin "L12") (pinfunction "GPIO_AD_B1_04_L12") (pintype "bidirectional"))
    )
    (net (code "91") (name "unconnected-(U1-GPIO_AD_B1_05-PadK12)") (class "Default")
      (node (ref "U1") (pin "K12") (pinfunction "GPIO_AD_B1_05_K12") (pintype "bidirectional"))
    )
    (net (code "92") (name "unconnected-(U1-GPIO_AD_B1_12-PadH12)") (class "Default")
      (node (ref "U1") (pin "H12") (pinfunction "GPIO_AD_B1_12_H12") (pintype "bidirectional"))
    )
    (net (code "93") (name "unconnected-(U1-GPIO_AD_B1_13-PadH11)") (class "Default")
      (node (ref "U1") (pin "H11") (pinfunction "GPIO_AD_B1_13_H11") (pintype "bidirectional"))
    )
    (net (code "94") (name "unconnected-(U1-GPIO_B0_04-PadC8)") (class "Default")
      (node (ref "U1") (pin "C8") (pinfunction "GPIO_B0_04_C8") (pintype "bidirectional"))
    )
    (net (code "95") (name "unconnected-(U1-GPIO_B0_05-PadB8)") (class "Default")
      (node (ref "U1") (pin "B8") (pinfunction "GPIO_B0_05_B8") (pintype "bidirectional"))
    )
    (net (code "96") (name "unconnected-(U1-GPIO_B0_06-PadA8)") (class "Default")
      (node (ref "U1") (pin "A8") (pinfunction "GPIO_B0_06_A8") (pintype "bidirectional"))
    )
    (net (code "97") (name "unconnected-(U1-GPIO_B0_07-PadA9)") (class "Default")
      (node (ref "U1") (pin "A9") (pinfunction "GPIO_B0_07_A9") (pintype "bidirectional"))
    )
    (net (code "98") (name "unconnected-(U1-GPIO_B0_08-PadB9)") (class "Default")
      (node (ref "U1") (pin "B9") (pinfunction "GPIO_B0_08_B9") (pintype "bidirectional"))
    )
    (net (code "99") (name "unconnected-(U1-GPIO_B0_09-PadC9)") (class "Default")
      (node (ref "U1") (pin "C9") (pinfunction "GPIO_B0_09_C9") (pintype "bidirectional"))
    )
    (net (code "100") (name "unconnected-(U1-GPIO_B0_11-PadA10)") (class "Default")
      (node (ref "U1") (pin "A10") (pinfunction "GPIO_B0_11_A10") (pintype "bidirectional"))
    )
    (net (code "101") (name "unconnected-(U1-GPIO_B0_14-PadE10)") (class "Default")
      (node (ref "U1") (pin "E10") (pinfunction "GPIO_B0_14_E10") (pintype "bidirectional"))
    )
    (net (code "102") (name "unconnected-(U1-GPIO_B0_15-PadE11)") (class "Default")
      (node (ref "U1") (pin "E11") (pinfunction "GPIO_B0_15_E11") (pintype "bidirectional"))
    )
    (net (code "103") (name "unconnected-(U1-GPIO_B1_02-PadC11)") (class "Default")
      (node (ref "U1") (pin "C11") (pinfunction "GPIO_B1_02_C11") (pintype "bidirectional"))
    )
    (net (code "104") (name "unconnected-(U1-GPIO_B1_03-PadD11)") (class "Default")
      (node (ref "U1") (pin "D11") (pinfunction "GPIO_B1_03_D11") (pintype "bidirectional"))
    )
    (net (code "105") (name "unconnected-(U1-GPIO_B1_04-PadE12)") (class "Default")
      (node (ref "U1") (pin "E12") (pinfunction "GPIO_B1_04_E12") (pintype "bidirectional"))
    )
    (net (code "106") (name "unconnected-(U1-GPIO_B1_05-PadD12)") (class "Default")
      (node (ref "U1") (pin "D12") (pinfunction "GPIO_B1_05_D12") (pintype "bidirectional"))
    )
    (net (code "107") (name "unconnected-(U1-GPIO_B1_06-PadC12)") (class "Default")
      (node (ref "U1") (pin "C12") (pinfunction "GPIO_B1_06_C12") (pintype "bidirectional"))
    )
    (net (code "108") (name "unconnected-(U1-GPIO_B1_07-PadB12)") (class "Default")
      (node (ref "U1") (pin "B12") (pinfunction "GPIO_B1_07_B12") (pintype "bidirectional"))
    )
    (net (code "109") (name "unconnected-(U1-GPIO_B1_08-PadA12)") (class "Default")
      (node (ref "U1") (pin "A12") (pinfunction "GPIO_B1_08_A12") (pintype "bidirectional"))
    )
    (net (code "110") (name "unconnected-(U1-GPIO_B1_09-PadA13)") (class "Default")
      (node (ref "U1") (pin "A13") (pinfunction "GPIO_B1_09_A13") (pintype "bidirectional"))
    )
    (net (code "111") (name "unconnected-(U1-GPIO_B1_10-PadB13)") (class "Default")
      (node (ref "U1") (pin "B13") (pinfunction "GPIO_B1_10_B13") (pintype "bidirectional"))
    )
    (net (code "112") (name "unconnected-(U1-GPIO_B1_11-PadC13)") (class "Default")
      (node (ref "U1") (pin "C13") (pinfunction "GPIO_B1_11_C13") (pintype "bidirectional"))
    )
    (net (code "113") (name "unconnected-(U1-GPIO_B1_12-PadD13)") (class "Default")
      (node (ref "U1") (pin "D13") (pinfunction "GPIO_B1_12_D13") (pintype "bidirectional"))
    )
    (net (code "114") (name "unconnected-(U1-GPIO_B1_13-PadD14)") (class "Default")
      (node (ref "U1") (pin "D14") (pinfunction "GPIO_B1_13_D14") (pintype "bidirectional"))
    )
    (net (code "115") (name "unconnected-(U1-GPIO_B1_14-PadC14)") (class "Default")
      (node (ref "U1") (pin "C14") (pinfunction "GPIO_B1_14_C14") (pintype "bidirectional"))
    )
    (net (code "116") (name "unconnected-(U1-GPIO_B1_15-PadB14)") (class "Default")
      (node (ref "U1") (pin "B14") (pinfunction "GPIO_B1_15_B14") (pintype "bidirectional"))
    )
    (net (code "117") (name "unconnected-(U1-GPIO_EMC_00-PadE3)") (class "Default")
      (node (ref "U1") (pin "E3") (pinfunction "GPIO_EMC_00_E3") (pintype "bidirectional"))
    )
    (net (code "118") (name "unconnected-(U1-GPIO_EMC_02-PadF4)") (class "Default")
      (node (ref "U1") (pin "F4") (pinfunction "GPIO_EMC_02_F4") (pintype "bidirectional"))
    )
    (net (code "119") (name "unconnected-(U1-GPIO_EMC_03-PadG4)") (class "Default")
      (node (ref "U1") (pin "G4") (pinfunction "GPIO_EMC_03_G4") (pintype "bidirectional"))
    )
    (net (code "120") (name "unconnected-(U1-GPIO_EMC_09-PadC2)") (class "Default")
      (node (ref "U1") (pin "C2") (pinfunction "GPIO_EMC_09_C2") (pintype "bidirectional"))
    )
    (net (code "121") (name "unconnected-(U1-GPIO_EMC_10-PadG1)") (class "Default")
      (node (ref "U1") (pin "G1") (pinfunction "GPIO_EMC_10_G1") (pintype "bidirectional"))
    )
    (net (code "122") (name "unconnected-(U1-GPIO_EMC_11-PadG3)") (class "Default")
      (node (ref "U1") (pin "G3") (pinfunction "GPIO_EMC_11_G3") (pintype "bidirectional"))
    )
    (net (code "123") (name "unconnected-(U1-GPIO_EMC_12-PadH1)") (class "Default")
      (node (ref "U1") (pin "H1") (pinfunction "GPIO_EMC_12_H1") (pintype "bidirectional"))
    )
    (net (code "124") (name "unconnected-(U1-GPIO_EMC_13-PadA6)") (class "Default")
      (node (ref "U1") (pin "A6") (pinfunction "GPIO_EMC_13_A6") (pintype "bidirectional"))
    )
    (net (code "125") (name "unconnected-(U1-GPIO_EMC_14-PadB6)") (class "Default")
      (node (ref "U1") (pin "B6") (pinfunction "GPIO_EMC_14_B6") (pintype "bidirectional"))
    )
    (net (code "126") (name "unconnected-(U1-GPIO_EMC_15-PadB1)") (class "Default")
      (node (ref "U1") (pin "B1") (pinfunction "GPIO_EMC_15_B1") (pintype "bidirectional"))
    )
    (net (code "127") (name "unconnected-(U1-GPIO_EMC_16-PadA5)") (class "Default")
      (node (ref "U1") (pin "A5") (pinfunction "GPIO_EMC_16_A5") (pintype "bidirectional"))
    )
    (net (code "128") (name "unconnected-(U1-GPIO_EMC_17-PadA4)") (class "Default")
      (node (ref "U1") (pin "A4") (pinfunction "GPIO_EMC_17_A4") (pintype "bidirectional"))
    )
    (net (code "129") (name "unconnected-(U1-GPIO_EMC_18-PadB2)") (class "Default")
      (node (ref "U1") (pin "B2") (pinfunction "GPIO_EMC_18_B2") (pintype "bidirectional"))
    )
    (net (code "130") (name "unconnected-(U1-GPIO_EMC_19-PadB4)") (class "Default")
      (node (ref "U1") (pin "B4") (pinfunction "GPIO_EMC_19_B4") (pintype "bidirectional"))
    )
    (net (code "131") (name "unconnected-(U1-GPIO_EMC_20-PadA3)") (class "Default")
      (node (ref "U1") (pin "A3") (pinfunction "GPIO_EMC_20_A3") (pintype "bidirectional"))
    )
    (net (code "132") (name "unconnected-(U1-GPIO_EMC_21-PadC1)") (class "Default")
      (node (ref "U1") (pin "C1") (pinfunction "GPIO_EMC_21_C1") (pintype "bidirectional"))
    )
    (net (code "133") (name "unconnected-(U1-GPIO_EMC_22-PadF1)") (class "Default")
      (node (ref "U1") (pin "F1") (pinfunction "GPIO_EMC_22_F1") (pintype "bidirectional"))
    )
    (net (code "134") (name "unconnected-(U1-GPIO_EMC_23-PadG2)") (class "Default")
      (node (ref "U1") (pin "G2") (pinfunction "GPIO_EMC_23_G2") (pintype "bidirectional"))
    )
    (net (code "135") (name "unconnected-(U1-GPIO_EMC_24-PadD3)") (class "Default")
      (node (ref "U1") (pin "D3") (pinfunction "GPIO_EMC_24_D3") (pintype "bidirectional"))
    )
    (net (code "136") (name "unconnected-(U1-GPIO_EMC_25-PadD2)") (class "Default")
      (node (ref "U1") (pin "D2") (pinfunction "GPIO_EMC_25_D2") (pintype "bidirectional"))
    )
    (net (code "137") (name "unconnected-(U1-GPIO_EMC_26-PadB3)") (class "Default")
      (node (ref "U1") (pin "B3") (pinfunction "GPIO_EMC_26_B3") (pintype "bidirectional"))
    )
    (net (code "138") (name "unconnected-(U1-GPIO_EMC_27-PadA2)") (class "Default")
      (node (ref "U1") (pin "A2") (pinfunction "GPIO_EMC_27_A2") (pintype "bidirectional"))
    )
    (net (code "139") (name "unconnected-(U1-GPIO_EMC_28-PadD1)") (class "Default")
      (node (ref "U1") (pin "D1") (pinfunction "GPIO_EMC_28_D1") (pintype "bidirectional"))
    )
    (net (code "140") (name "unconnected-(U1-GPIO_EMC_29-PadE1)") (class "Default")
      (node (ref "U1") (pin "E1") (pinfunction "GPIO_EMC_29_E1") (pintype "bidirectional"))
    )
    (net (code "141") (name "unconnected-(U1-GPIO_EMC_30-PadC6)") (class "Default")
      (node (ref "U1") (pin "C6") (pinfunction "GPIO_EMC_30_C6") (pintype "bidirectional"))
    )
    (net (code "142") (name "unconnected-(U1-GPIO_EMC_33-PadC4)") (class "Default")
      (node (ref "U1") (pin "C4") (pinfunction "GPIO_EMC_33_C4") (pintype "bidirectional"))
    )
    (net (code "143") (name "unconnected-(U1-GPIO_EMC_34-PadD4)") (class "Default")
      (node (ref "U1") (pin "D4") (pinfunction "GPIO_EMC_34_D4") (pintype "bidirectional"))
    )
    (net (code "144") (name "unconnected-(U1-GPIO_EMC_35-PadE5)") (class "Default")
      (node (ref "U1") (pin "E5") (pinfunction "GPIO_EMC_35_E5") (pintype "bidirectional"))
    )
    (net (code "145") (name "unconnected-(U1-GPIO_EMC_38-PadD6)") (class "Default")
      (node (ref "U1") (pin "D6") (pinfunction "GPIO_EMC_38_D6") (pintype "bidirectional"))
    )
    (net (code "146") (name "unconnected-(U1-GPIO_EMC_39-PadB7)") (class "Default")
      (node (ref "U1") (pin "B7") (pinfunction "GPIO_EMC_39_B7") (pintype "bidirectional"))
    )
    (net (code "147") (name "unconnected-(U1-GPIO_EMC_40-PadA7)") (class "Default")
      (node (ref "U1") (pin "A7") (pinfunction "GPIO_EMC_40_A7") (pintype "bidirectional"))
    )
    (net (code "148") (name "unconnected-(U1-GPIO_EMC_41-PadC7)") (class "Default")
      (node (ref "U1") (pin "C7") (pinfunction "GPIO_EMC_41_C7") (pintype "bidirectional"))
    )
    (net (code "149") (name "unconnected-(U1-GPIO_SD_B1_00-PadL5)") (class "Default")
      (node (ref "U1") (pin "L5") (pinfunction "GPIO_SD_B1_00_L5") (pintype "bidirectional"))
    )
    (net (code "150") (name "unconnected-(U1-GPIO_SD_B1_01-PadM5)") (class "Default")
      (node (ref "U1") (pin "M5") (pinfunction "GPIO_SD_B1_01_M5") (pintype "bidirectional"))
    )
    (net (code "151") (name "unconnected-(U1-GPIO_SD_B1_02-PadM3)") (class "Default")
      (node (ref "U1") (pin "M3") (pinfunction "GPIO_SD_B1_02_M3") (pintype "bidirectional"))
    )
    (net (code "152") (name "unconnected-(U1-GPIO_SD_B1_03-PadM4)") (class "Default")
      (node (ref "U1") (pin "M4") (pinfunction "GPIO_SD_B1_03_M4") (pintype "bidirectional"))
    )
    (net (code "153") (name "unconnected-(U1-GPIO_SD_B1_04-PadP2)") (class "Default")
      (node (ref "U1") (pin "P2") (pinfunction "GPIO_SD_B1_04_P2") (pintype "bidirectional"))
    )
    (net (code "154") (name "unconnected-(U1-GPIO_SD_B1_05-PadN3)") (class "Default")
      (node (ref "U1") (pin "N3") (pinfunction "GPIO_SD_B1_05_N3") (pintype "bidirectional"))
    )
    (net (code "155") (name "unconnected-(U1-NGND_KEL0-PadK9)") (class "Default")
      (node (ref "U1") (pin "K9") (pinfunction "NGND_KEL0_K9") (pintype "bidirectional"))
    )
    (net (code "156") (name "unconnected-(U1-PMIC_STBY_REQ-PadL7)") (class "Default")
      (node (ref "U1") (pin "L7") (pinfunction "PMIC_STBY_REQ_L7") (pintype "bidirectional"))
    )
    (net (code "157") (name "unconnected-(U1-TEST_MODE-PadK6)") (class "Default")
      (node (ref "U1") (pin "K6") (pinfunction "TEST_MODE_K6") (pintype "bidirectional"))
    )
    (net (code "158") (name "unconnected-(U1-USB_OTG1_CHD_B-PadN12)") (class "Default")
      (node (ref "U1") (pin "N12") (pinfunction "USB_OTG1_CHD_B_N12") (pintype "bidirectional"))
    )
    (net (code "159") (name "unconnected-(U1-WAKEUP-PadL6)") (class "Default")
      (node (ref "U1") (pin "L6") (pinfunction "WAKEUP_L6") (pintype "bidirectional"))
    )
  )
)
